# 4_TFT_LCD.net
KiCad netlist of a schematic drawn in Altium Designer
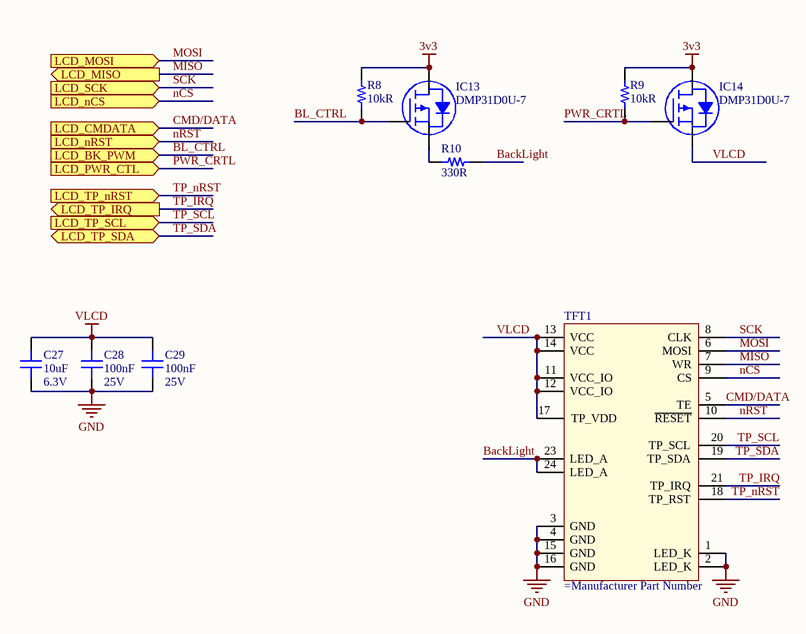
[diagram p0: [4] TFT LCD.SchDoc]

(export (version "E")
  (design (tool "Eeschema 10.0.6"))
  (components
    (comp (ref "C27")
      (value "10uF")
      (footprint "CAP 0402/1005")
      (description "0402 10 uF 6.3 V ±20 % Tolerance X5R Surface Mount Multilayer Ceramic Capacitor")
      (fields
        (field (name "MANUFACTURER") "Murata")
        (field (name "MANUFACTURER PART NUMBER") "GRM155R60J106ME15D")
        (field (name "VOLTAGE RATING") "6.3V")
      )
      (libsource (lib "yildizIoT Library") (part "Capacitor - Ceramic"))
    )
    (comp (ref "C28")
      (value "100nF")
      (footprint "CAP 0402/1005")
      (description "Cap Ceramic 0.1uF 25V X5R 10% Pad SMD 0402 85°C T/R / Multi Layer Ceramic Capacitor (MLCC)")
      (fields
        (field (name "MANUFACTURER") "Samsung")
        (field (name "MANUFACTURER PART NUMBER") "CL05A104KA5NNNC")
        (field (name "VOLTAGE RATING (DC)") "25V")
      )
      (libsource (lib "yildizIoT Library") (part "Capacitor - Ceramic"))
    )
    (comp (ref "C29")
      (value "100nF")
      (footprint "CAP 0402/1005")
      (description "Cap Ceramic 0.1uF 25V X5R 10% Pad SMD 0402 85°C T/R / Multi Layer Ceramic Capacitor (MLCC)")
      (fields
        (field (name "MANUFACTURER") "Samsung")
        (field (name "MANUFACTURER PART NUMBER") "CL05A104KA5NNNC")
        (field (name "VOLTAGE RATING (DC)") "25V")
      )
      (libsource (lib "yildizIoT Library") (part "Capacitor - Ceramic"))
    )
    (comp (ref "IC13")
      (value "DMP31D0U-7")
      (footprint "DIODES SOT-23-3")
      (description "MOSFET P-CH 30V 530MA SOT23")
      (fields (field (name "MANUFACTURER") "Diodes Incorporated"))
      (libsource (lib "Celestial Altium Library - altium_library") (part "DIODES MOSFET P-CH SOT-23-3"))
    )
    (comp (ref "IC14")
      (value "DMP31D0U-7")
      (footprint "DIODES SOT-23-3")
      (description "MOSFET P-CH 30V 530MA SOT23")
      (fields (field (name "MANUFACTURER") "Diodes Incorporated"))
      (libsource (lib "Celestial Altium Library - altium_library") (part "DIODES MOSFET P-CH SOT-23-3"))
    )
    (comp (ref "R8")
      (value "10kR")
      (footprint "RES 0402/1005")
      (description "Res Thick Film 0402 10K Ohm 1% 0.063W(1/16W) ±100ppm/C Pad SMD Automotive T/R")
      (fields
        (field (name "MANUFACTURER") "Stackpole Electronics")
        (field (name "MANUFACTURER PART NUMBER") "RMCF0402FT10K0")
      )
      (libsource (lib "yildizIoT Library") (part "Resistor_Chip"))
    )
    (comp (ref "R9")
      (value "10kR")
      (footprint "RES 0402/1005")
      (description "Res Thick Film 0402 10K Ohm 1% 0.063W(1/16W) ±100ppm/C Pad SMD Automotive T/R")
      (fields
        (field (name "MANUFACTURER") "Stackpole Electronics")
        (field (name "MANUFACTURER PART NUMBER") "RMCF0402FT10K0")
      )
      (libsource (lib "yildizIoT Library") (part "Resistor_Chip"))
    )
    (comp (ref "R10")
      (value "330R")
      (footprint "RES 0402/1005")
      (description "Res Thick Film 0402 330 Ohm 1% 0.063W(1/16W) ±100ppm/C Pad SMD T/R")
      (fields
        (field (name "MANUFACTURER") "Walsin Technologies")
        (field (name "MANUFACTURER PART NUMBER") "WR04X3300FTL")
      )
      (libsource (lib "yildizIoT Library") (part "Resistor_Chip"))
    )
    (comp (ref "TFT1")
      (value "~")
      (footprint "EASTRISE ER-TFT1.28-2")
      (description "ER-TFT1.28-2 TFT LCD Display Datasheet")
      (libsource (lib "yildizIoT Library") (part "EASTRISE ER-TFT1.28-2"))
    )
  )
  (nets
    (net (code "1") (name "/BL_CTRL") (class "Default")
      (node (ref "IC13") (pin "1") (pinfunction "G_1") (pintype "passive"))
      (node (ref "R8") (pin "1") (pinfunction "1_1") (pintype "passive"))
    )
    (net (code "2") (name "/BackLight") (class "Default")
      (node (ref "R10") (pin "2") (pinfunction "2_2") (pintype "passive"))
      (node (ref "TFT1") (pin "23") (pinfunction "LED_A_23") (pintype "passive"))
      (node (ref "TFT1") (pin "24") (pinfunction "LED_A_24") (pintype "passive"))
    )
    (net (code "3") (name "/CMD{slash}DATA") (class "Default")
      (node (ref "TFT1") (pin "5") (pinfunction "TE_5") (pintype "passive"))
    )
    (net (code "4") (name "/MISO") (class "Default")
      (node (ref "TFT1") (pin "7") (pinfunction "WR_7") (pintype "passive"))
    )
    (net (code "5") (name "/MOSI") (class "Default")
      (node (ref "TFT1") (pin "6") (pinfunction "MOSI_6") (pintype "passive"))
    )
    (net (code "6") (name "/PWR_CRTL") (class "Default")
      (node (ref "IC14") (pin "1") (pinfunction "G_1") (pintype "passive"))
      (node (ref "R9") (pin "1") (pinfunction "1_1") (pintype "passive"))
    )
    (net (code "7") (name "/SCK") (class "Default")
      (node (ref "TFT1") (pin "8") (pinfunction "CLK_8") (pintype "passive"))
    )
    (net (code "8") (name "/TP_IRQ") (class "Default")
      (node (ref "TFT1") (pin "21") (pinfunction "TP_IRQ_21") (pintype "passive"))
    )
    (net (code "9") (name "/TP_SCL") (class "Default")
      (node (ref "TFT1") (pin "20") (pinfunction "TP_SCL_20") (pintype "passive"))
    )
    (net (code "10") (name "/TP_SDA") (class "Default")
      (node (ref "TFT1") (pin "19") (pinfunction "TP_SDA_19") (pintype "passive"))
    )
    (net (code "11") (name "/TP_nRST") (class "Default")
      (node (ref "TFT1") (pin "18") (pinfunction "TP_RST_18") (pintype "passive"))
    )
    (net (code "12") (name "/nCS") (class "Default")
      (node (ref "TFT1") (pin "9") (pinfunction "CS_9") (pintype "passive"))
    )
    (net (code "13") (name "/nRST") (class "Default")
      (node (ref "TFT1") (pin "10") (pinfunction "~{RESET}_10") (pintype "passive"))
    )
    (net (code "14") (name "3v3") (class "Default")
      (node (ref "IC13") (pin "3") (pinfunction "D_3") (pintype "passive"))
      (node (ref "IC14") (pin "3") (pinfunction "D_3") (pintype "passive"))
      (node (ref "R8") (pin "2") (pinfunction "2_2") (pintype "passive"))
      (node (ref "R9") (pin "2") (pinfunction "2_2") (pintype "passive"))
    )
    (net (code "15") (name "GND") (class "Default")
      (node (ref "C27") (pin "1") (pinfunction "1_1") (pintype "passive"))
      (node (ref "C28") (pin "1") (pinfunction "1_1") (pintype "passive"))
      (node (ref "C29") (pin "1") (pinfunction "1_1") (pintype "passive"))
      (node (ref "TFT1") (pin "1") (pinfunction "LED_K_1") (pintype "passive"))
      (node (ref "TFT1") (pin "15") (pinfunction "GND_15") (pintype "passive"))
      (node (ref "TFT1") (pin "16") (pinfunction "GND_16") (pintype "passive"))
      (node (ref "TFT1") (pin "2") (pinfunction "LED_K_2") (pintype "passive"))
      (node (ref "TFT1") (pin "3") (pinfunction "GND_3") (pintype "passive"))
      (node (ref "TFT1") (pin "4") (pinfunction "GND_4") (pintype "passive"))
    )
    (net (code "16") (name "Net-(IC13-S)") (class "Default")
      (node (ref "IC13") (pin "2") (pinfunction "S_2") (pintype "passive"))
      (node (ref "R10") (pin "1") (pinfunction "1_1") (pintype "passive"))
    )
    (net (code "17") (name "VLCD") (class "Default")
      (node (ref "C27") (pin "2") (pinfunction "2_2") (pintype "passive"))
      (node (ref "C28") (pin "2") (pinfunction "2_2") (pintype "passive"))
      (node (ref "C29") (pin "2") (pinfunction "2_2") (pintype "passive"))
      (node (ref "IC14") (pin "2") (pinfunction "S_2") (pintype "passive"))
      (node (ref "TFT1") (pin "11") (pinfunction "VCC_IO_11") (pintype "passive"))
      (node (ref "TFT1") (pin "12") (pinfunction "VCC_IO_12") (pintype "passive"))
      (node (ref "TFT1") (pin "13") (pinfunction "VCC_13") (pintype "passive"))
      (node (ref "TFT1") (pin "14") (pinfunction "VCC_14") (pintype "passive"))
      (node (ref "TFT1") (pin "17") (pinfunction "TP_VDD_17") (pintype "passive"))
    )
  )
)
